# Schematic_1.net
KiCad netlist of a schematic drawn in Altium Designer
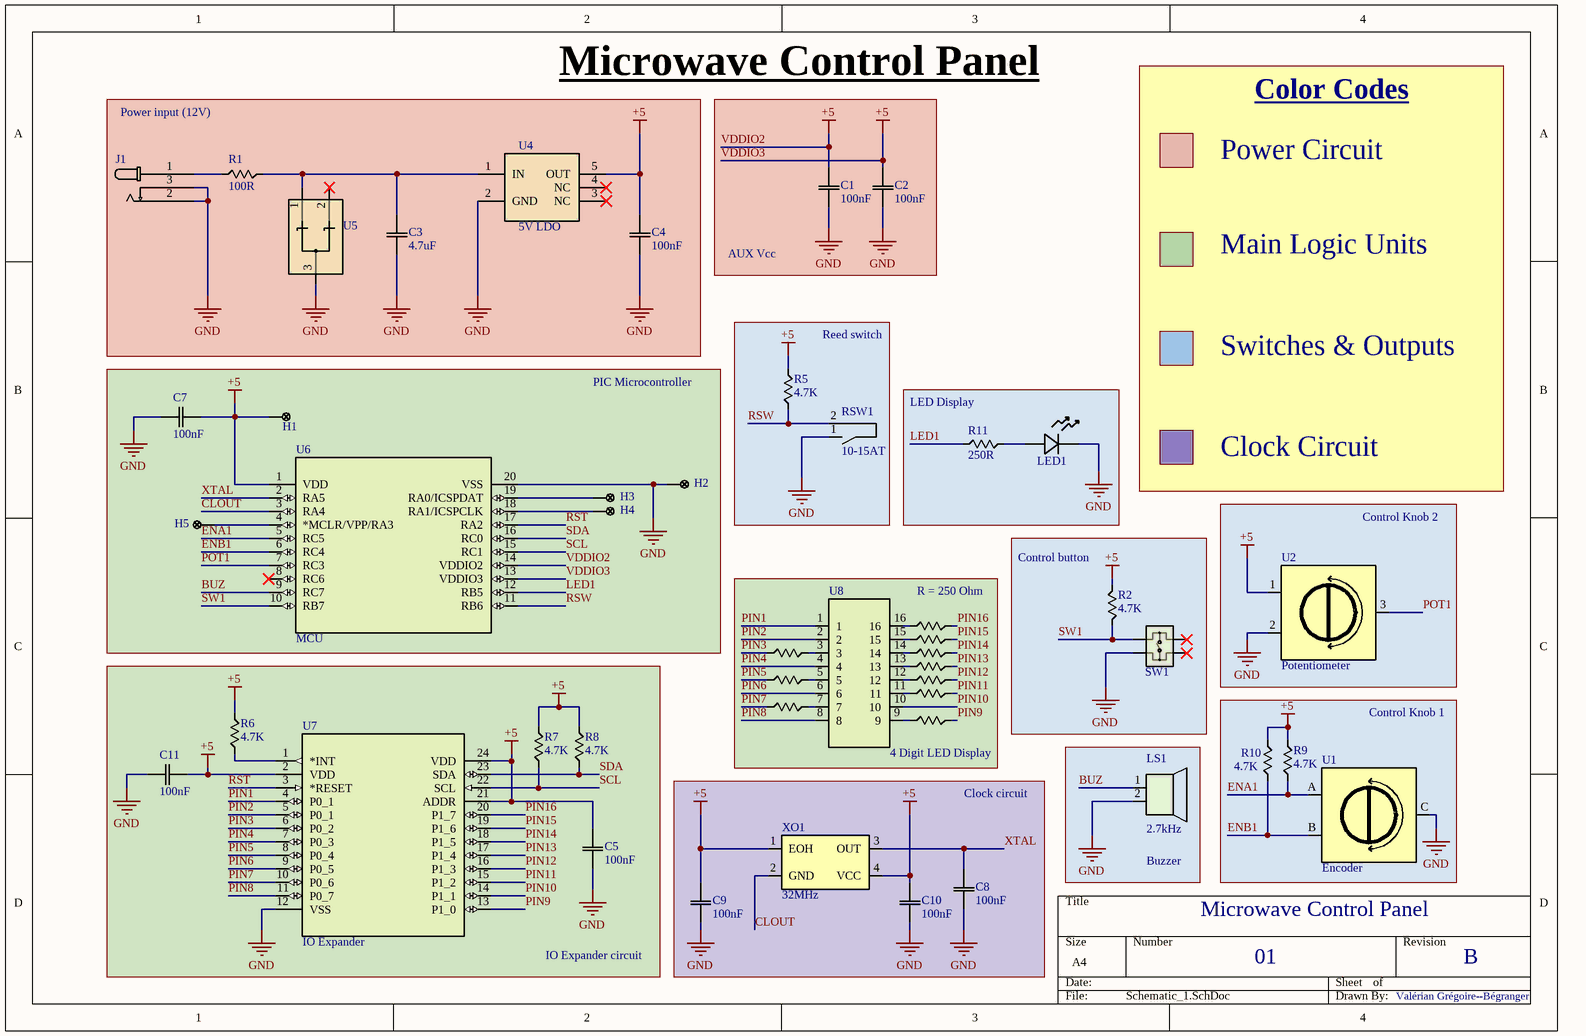
[diagram p0: Schematic_1.SchDoc]

(export (version "E")
  (design (tool "Eeschema 10.0.6"))
  (components
    (comp (ref "C1")
      (value "100nF")
      (footprint "0805_AVX")
      (libsource (lib "Schematic_Library_1") (part "08051C103JAT2A"))
    )
    (comp (ref "C2")
      (value "100nF")
      (footprint "0805_AVX")
      (libsource (lib "Schematic_Library_1") (part "08051C103JAT2A"))
    )
    (comp (ref "C3")
      (value "4.7uF")
      (footprint "CAP_08051A0R8CAT2A_AVX")
      (libsource (lib "Schematic_Library_1") (part "08053C472K4Z2A"))
    )
    (comp (ref "C4")
      (value "100nF")
      (footprint "0805_AVX")
      (libsource (lib "Schematic_Library_1") (part "08051C103JAT2A"))
    )
    (comp (ref "C5")
      (value "100nF")
      (footprint "0805_AVX")
      (libsource (lib "Schematic_Library_1") (part "08051C103JAT2A"))
    )
    (comp (ref "C7")
      (value "100nF")
      (footprint "0805_AVX")
      (libsource (lib "Schematic_Library_1") (part "08051C103JAT2A"))
    )
    (comp (ref "C8")
      (value "100nF")
      (footprint "0805_AVX")
      (libsource (lib "Schematic_Library_1") (part "08051C103JAT2A"))
    )
    (comp (ref "C9")
      (value "100nF")
      (footprint "0805_AVX")
      (libsource (lib "Schematic_Library_1") (part "08051C103JAT2A"))
    )
    (comp (ref "C10")
      (value "100nF")
      (footprint "0805_AVX")
      (libsource (lib "Schematic_Library_1") (part "08051C103JAT2A"))
    )
    (comp (ref "C11")
      (value "100nF")
      (footprint "0805_AVX")
      (libsource (lib "Schematic_Library_1") (part "08051C103JAT2A"))
    )
    (comp (ref "H1")
      (value "Output")
      (footprint "1 pin header")
      (libsource (lib "Schematic_Library_1") (part "1 pin header"))
    )
    (comp (ref "H2")
      (value "Output")
      (footprint "1 pin header")
      (libsource (lib "Schematic_Library_1") (part "1 pin header"))
    )
    (comp (ref "H3")
      (value "Output")
      (footprint "1 pin header")
      (libsource (lib "Schematic_Library_1") (part "1 pin header"))
    )
    (comp (ref "H4")
      (value "Output")
      (footprint "1 pin header")
      (libsource (lib "Schematic_Library_1") (part "1 pin header"))
    )
    (comp (ref "H5")
      (value "Output")
      (footprint "1 pin header")
      (libsource (lib "Schematic_Library_1") (part "1 pin header"))
    )
    (comp (ref "J1")
      (value "PJ-002A")
      (footprint "PJ-002A_CUD")
      (description "DC power plug")
      (libsource (lib "Schematic_Library_1") (part "PJ-002A"))
    )
    (comp (ref "LED1")
      (value "156120VS75300")
      (footprint "LED_VS75300_WRE")
      (description "LED")
      (libsource (lib "Schematic_Library_1") (part "156120VS75300"))
    )
    (comp (ref "LS1")
      (value "2.7kHz")
      (footprint "CMI-9605IC_CUD")
      (description "Buzzer")
      (libsource (lib "Schematic_Library_1") (part "CMI-9605IC-0380T"))
    )
    (comp (ref "R1")
      (value "100R")
      (footprint "0805_VIS")
      (libsource (lib "Schematic_Library_1") (part "RCG080510R0FKEA"))
    )
    (comp (ref "R2")
      (value "4.7K")
      (footprint "RES_1220_SUS")
      (libsource (lib "Schematic_Library_1") (part "RG2012P-472-B-T5"))
    )
    (comp (ref "R3")
      (value "250R")
      (footprint "0805_VIS")
      (libsource (lib "Schematic_Library_1") (part "RNCF0805TKY250R"))
    )
    (comp (ref "R4")
      (value "250R")
      (footprint "0805_VIS")
      (libsource (lib "Schematic_Library_1") (part "RNCF0805TKY250R"))
    )
    (comp (ref "R5")
      (value "4.7K")
      (footprint "RES_1220_SUS")
      (libsource (lib "Schematic_Library_1") (part "RG2012P-472-B-T5"))
    )
    (comp (ref "R6")
      (value "4.7K")
      (footprint "RES_1220_SUS")
      (libsource (lib "Schematic_Library_1") (part "RG2012P-472-B-T5"))
    )
    (comp (ref "R7")
      (value "4.7K")
      (footprint "RES_1220_SUS")
      (libsource (lib "Schematic_Library_1") (part "RG2012P-472-B-T5"))
    )
    (comp (ref "R8")
      (value "4.7K")
      (footprint "RES_1220_SUS")
      (libsource (lib "Schematic_Library_1") (part "RG2012P-472-B-T5"))
    )
    (comp (ref "R9")
      (value "4.7K")
      (footprint "RES_1220_SUS")
      (libsource (lib "Schematic_Library_1") (part "RG2012P-472-B-T5"))
    )
    (comp (ref "R10")
      (value "4.7K")
      (footprint "RES_1220_SUS")
      (libsource (lib "Schematic_Library_1") (part "RG2012P-472-B-T5"))
    )
    (comp (ref "R11")
      (value "250R")
      (footprint "0805_VIS")
      (libsource (lib "Schematic_Library_1") (part "RNCF0805TKY250R"))
    )
    (comp (ref "R12")
      (value "250R")
      (footprint "0805_VIS")
      (libsource (lib "Schematic_Library_1") (part "RNCF0805TKY250R"))
    )
    (comp (ref "R13")
      (value "250R")
      (footprint "0805_VIS")
      (libsource (lib "Schematic_Library_1") (part "RNCF0805TKY250R"))
    )
    (comp (ref "R14")
      (value "250R")
      (footprint "0805_VIS")
      (libsource (lib "Schematic_Library_1") (part "RNCF0805TKY250R"))
    )
    (comp (ref "R15")
      (value "250R")
      (footprint "0805_VIS")
      (libsource (lib "Schematic_Library_1") (part "RNCF0805TKY250R"))
    )
    (comp (ref "R16")
      (value "250R")
      (footprint "0805_VIS")
      (libsource (lib "Schematic_Library_1") (part "RNCF0805TKY250R"))
    )
    (comp (ref "R17")
      (value "250R")
      (footprint "0805_VIS")
      (libsource (lib "Schematic_Library_1") (part "RNCF0805TKY250R"))
    )
    (comp (ref "R18")
      (value "250R")
      (footprint "0805_VIS")
      (libsource (lib "Schematic_Library_1") (part "RNCF0805TKY250R"))
    )
    (comp (ref "R19")
      (value "250R")
      (footprint "0805_VIS")
      (libsource (lib "Schematic_Library_1") (part "RNCF0805TKY250R"))
    )
    (comp (ref "RSW1")
      (value "10-15AT")
      (footprint "GP56010-15")
      (description "Reed switch")
      (libsource (lib "Schematic_Library_1") (part "GP56010-15"))
    )
    (comp (ref "SW1")
      (value "TS02-66-160-BK-100-LCR-D")
      (footprint "TS02-66-160-BK-100-LCR-D")
      (description "Push button")
      (libsource (lib "Schematic_Library_1") (part "TS02-66-160-BK-100-LCR-D"))
    )
    (comp (ref "U1")
      (value "Encoder")
      (footprint "288T232R161A1")
      (description "2b Encoder")
      (libsource (lib "Schematic_Library_1") (part "288T232R161A1"))
    )
    (comp (ref "U2")
      (value "Potentiometer")
      (footprint "2002111655")
      (libsource (lib "Schematic_Library_1") (part "2002111655"))
    )
    (comp (ref "U4")
      (value "5V LDO")
      (footprint "SOT-23-5-DBV_TEX")
      (libsource (lib "Schematic_Library_1") (part "TPS7B92050DBVR"))
    )
    (comp (ref "U5")
      (value "MMBZ16VAT-QR")
      (footprint "SOT_SM712")
      (description "13V TVS")
      (libsource (lib "Schematic_Library_1") (part "MMBZ16VAT-QR"))
    )
    (comp (ref "U6")
      (value "MCU")
      (footprint "SOIC20_SO_MCH")
      (description "PIC MCU")
      (libsource (lib "Schematic_Library_1") (part "PIC18F15Q20T-ISO"))
    )
    (comp (ref "U7")
      (value "IO Expander")
      (footprint "TSSOP24_4P5X7P9_NXP")
      (description "16 I/O expander")
      (libsource (lib "Schematic_Library_1") (part "PCAL6416APW"))
    )
    (comp (ref "U8")
      (value "LED Display")
      (footprint "TDCG1060M_VIS")
      (description "4 digit LED display")
      (libsource (lib "Schematic_Library_1") (part "TDCR1060M"))
    )
    (comp (ref "XO1")
      (value "32MHz")
      (footprint "CB3-3C-64M0000")
      (description "32MHz Clock")
      (libsource (lib "Schematic_Library_1") (part "FO7HHADM320-T1"))
    )
  )
  (nets
    (net (code "1") (name "+5") (class "Default")
      (node (ref "C1") (pin "2") (pinfunction "2_2") (pintype "passive"))
      (node (ref "C10") (pin "2") (pinfunction "2_2") (pintype "passive"))
      (node (ref "C11") (pin "2") (pinfunction "2_2") (pintype "passive"))
      (node (ref "C2") (pin "2") (pinfunction "2_2") (pintype "passive"))
      (node (ref "C4") (pin "2") (pinfunction "2_2") (pintype "passive"))
      (node (ref "C5") (pin "2") (pinfunction "2_2") (pintype "passive"))
      (node (ref "C7") (pin "2") (pinfunction "2_2") (pintype "passive"))
      (node (ref "C9") (pin "2") (pinfunction "2_2") (pintype "passive"))
      (node (ref "H1") (pin "1") (pinfunction "1_1") (pintype "passive"))
      (node (ref "R10") (pin "2") (pinfunction "2_2") (pintype "passive"))
      (node (ref "R2") (pin "2") (pinfunction "2_2") (pintype "passive"))
      (node (ref "R5") (pin "2") (pinfunction "2_2") (pintype "passive"))
      (node (ref "R6") (pin "2") (pinfunction "2_2") (pintype "passive"))
      (node (ref "R7") (pin "2") (pinfunction "2_2") (pintype "passive"))
      (node (ref "R8") (pin "2") (pinfunction "2_2") (pintype "passive"))
      (node (ref "R9") (pin "2") (pinfunction "2_2") (pintype "passive"))
      (node (ref "U2") (pin "1") (pinfunction "1_1") (pintype "passive"))
      (node (ref "U4") (pin "5") (pinfunction "OUT_5") (pintype "passive"))
      (node (ref "U6") (pin "1") (pinfunction "VDD_1") (pintype "passive"))
      (node (ref "U6") (pin "13") (pinfunction "VDDIO3_13") (pintype "bidirectional"))
      (node (ref "U6") (pin "14") (pinfunction "VDDIO2_14") (pintype "bidirectional"))
      (node (ref "U7") (pin "2") (pinfunction "VDD_2") (pintype "passive"))
      (node (ref "U7") (pin "21") (pinfunction "ADDR_21") (pintype "passive"))
      (node (ref "U7") (pin "24") (pinfunction "VDD_24") (pintype "passive"))
      (node (ref "XO1") (pin "1") (pinfunction "EOH_1") (pintype "passive"))
      (node (ref "XO1") (pin "4") (pinfunction "VCC_4") (pintype "passive"))
    )
    (net (code "2") (name "/BUZ") (class "Default")
      (node (ref "LS1") (pin "1") (pinfunction "1_1") (pintype "passive"))
      (node (ref "U6") (pin "9") (pinfunction "RC7_9") (pintype "bidirectional"))
    )
    (net (code "3") (name "/CLOUT") (class "Default")
      (node (ref "U6") (pin "3") (pinfunction "RA4_3") (pintype "bidirectional"))
      (node (ref "XO1") (pin "2") (pinfunction "GND_2") (pintype "passive"))
    )
    (net (code "4") (name "/ENA1") (class "Default")
      (node (ref "R9") (pin "1") (pinfunction "1_1") (pintype "passive"))
      (node (ref "U1") (pin "A") (pinfunction "A_A") (pintype "passive"))
      (node (ref "U6") (pin "5") (pinfunction "RC5_5") (pintype "bidirectional"))
    )
    (net (code "5") (name "/ENB1") (class "Default")
      (node (ref "R10") (pin "1") (pinfunction "1_1") (pintype "passive"))
      (node (ref "U1") (pin "B") (pinfunction "B_B") (pintype "passive"))
      (node (ref "U6") (pin "6") (pinfunction "RC4_6") (pintype "bidirectional"))
    )
    (net (code "6") (name "/LED1") (class "Default")
      (node (ref "R11") (pin "1") (pinfunction "1_1") (pintype "passive"))
      (node (ref "U6") (pin "12") (pinfunction "RB5_12") (pintype "bidirectional"))
    )
    (net (code "7") (name "/PIN1") (class "Default")
      (node (ref "U7") (pin "4") (pinfunction "P0_1_4") (pintype "bidirectional"))
      (node (ref "U8") (pin "1") (pinfunction "1_1") (pintype "passive"))
    )
    (net (code "8") (name "/PIN2") (class "Default")
      (node (ref "U7") (pin "5") (pinfunction "P0_1_5") (pintype "bidirectional"))
      (node (ref "U8") (pin "2") (pinfunction "2_2") (pintype "passive"))
    )
    (net (code "9") (name "/PIN3") (class "Default")
      (node (ref "R12") (pin "1") (pinfunction "1_1") (pintype "passive"))
      (node (ref "U7") (pin "6") (pinfunction "P0_2_6") (pintype "bidirectional"))
    )
    (net (code "10") (name "/PIN4") (class "Default")
      (node (ref "U7") (pin "7") (pinfunction "P0_3_7") (pintype "bidirectional"))
      (node (ref "U8") (pin "4") (pinfunction "4_4") (pintype "passive"))
    )
    (net (code "11") (name "/PIN5") (class "Default")
      (node (ref "R15") (pin "1") (pinfunction "1_1") (pintype "passive"))
      (node (ref "U7") (pin "8") (pinfunction "P0_4_8") (pintype "bidirectional"))
    )
    (net (code "12") (name "/PIN6") (class "Default")
      (node (ref "U7") (pin "9") (pinfunction "P0_5_9") (pintype "bidirectional"))
      (node (ref "U8") (pin "6") (pinfunction "6_6") (pintype "passive"))
    )
    (net (code "13") (name "/PIN7") (class "Default")
      (node (ref "R18") (pin "1") (pinfunction "1_1") (pintype "passive"))
      (node (ref "U7") (pin "10") (pinfunction "P0_6_10") (pintype "bidirectional"))
    )
    (net (code "14") (name "/PIN8") (class "Default")
      (node (ref "U7") (pin "11") (pinfunction "P0_7_11") (pintype "bidirectional"))
      (node (ref "U8") (pin "8") (pinfunction "8_8") (pintype "passive"))
    )
    (net (code "15") (name "/PIN9") (class "Default")
      (node (ref "R19") (pin "2") (pinfunction "2_2") (pintype "passive"))
      (node (ref "U7") (pin "13") (pinfunction "P1_0_13") (pintype "bidirectional"))
    )
    (net (code "16") (name "/PIN10") (class "Default")
      (node (ref "U7") (pin "14") (pinfunction "P1_1_14") (pintype "bidirectional"))
      (node (ref "U8") (pin "10") (pinfunction "10_10") (pintype "passive"))
    )
    (net (code "17") (name "/PIN11") (class "Default")
      (node (ref "R17") (pin "2") (pinfunction "2_2") (pintype "passive"))
      (node (ref "U7") (pin "15") (pinfunction "P1_2_15") (pintype "bidirectional"))
    )
    (net (code "18") (name "/PIN12") (class "Default")
      (node (ref "R16") (pin "2") (pinfunction "2_2") (pintype "passive"))
      (node (ref "U7") (pin "16") (pinfunction "P1_3_16") (pintype "bidirectional"))
    )
    (net (code "19") (name "/PIN13") (class "Default")
      (node (ref "R14") (pin "2") (pinfunction "2_2") (pintype "passive"))
      (node (ref "U7") (pin "17") (pinfunction "P1_4_17") (pintype "bidirectional"))
    )
    (net (code "20") (name "/PIN14") (class "Default")
      (node (ref "R13") (pin "2") (pinfunction "2_2") (pintype "passive"))
      (node (ref "U7") (pin "18") (pinfunction "P1_5_18") (pintype "bidirectional"))
    )
    (net (code "21") (name "/PIN15") (class "Default")
      (node (ref "R4") (pin "2") (pinfunction "2_2") (pintype "passive"))
      (node (ref "U7") (pin "19") (pinfunction "P1_6_19") (pintype "bidirectional"))
    )
    (net (code "22") (name "/PIN16") (class "Default")
      (node (ref "R3") (pin "2") (pinfunction "2_2") (pintype "passive"))
      (node (ref "U7") (pin "20") (pinfunction "P1_7_20") (pintype "bidirectional"))
    )
    (net (code "23") (name "/POT1") (class "Default")
      (node (ref "U2") (pin "3") (pinfunction "3_3") (pintype "passive"))
      (node (ref "U6") (pin "7") (pinfunction "RC3_7") (pintype "bidirectional"))
    )
    (net (code "24") (name "/RST") (class "Default")
      (node (ref "U6") (pin "17") (pinfunction "RA2_17") (pintype "bidirectional"))
      (node (ref "U7") (pin "3") (pinfunction "*RESET_3") (pintype "input"))
    )
    (net (code "25") (name "/RSW") (class "Default")
      (node (ref "R5") (pin "1") (pinfunction "1_1") (pintype "passive"))
      (node (ref "RSW1") (pin "2") (pinfunction "2_2") (pintype "passive"))
      (node (ref "U6") (pin "11") (pinfunction "RB6_11") (pintype "bidirectional"))
    )
    (net (code "26") (name "/SCL") (class "Default")
      (node (ref "R7") (pin "1") (pinfunction "1_1") (pintype "passive"))
      (node (ref "U6") (pin "15") (pinfunction "RC1_15") (pintype "bidirectional"))
      (node (ref "U7") (pin "22") (pinfunction "SCL_22") (pintype "input"))
    )
    (net (code "27") (name "/SDA") (class "Default")
      (node (ref "R8") (pin "1") (pinfunction "1_1") (pintype "passive"))
      (node (ref "U6") (pin "16") (pinfunction "RC0_16") (pintype "bidirectional"))
      (node (ref "U7") (pin "23") (pinfunction "SDA_23") (pintype "bidirectional"))
    )
    (net (code "28") (name "/SW1") (class "Default")
      (node (ref "R2") (pin "1") (pinfunction "1_1") (pintype "passive"))
      (node (ref "SW1") (pin "1") (pinfunction "2_1") (pintype "passive"))
      (node (ref "U6") (pin "10") (pinfunction "RB7_10") (pintype "bidirectional"))
    )
    (net (code "29") (name "/XTAL") (class "Default")
      (node (ref "C8") (pin "2") (pinfunction "2_2") (pintype "passive"))
      (node (ref "U6") (pin "2") (pinfunction "RA5_2") (pintype "bidirectional"))
      (node (ref "XO1") (pin "3") (pinfunction "OUT_3") (pintype "passive"))
    )
    (net (code "30") (name "GND") (class "Default")
      (node (ref "C1") (pin "1") (pinfunction "1_1") (pintype "passive"))
      (node (ref "C10") (pin "1") (pinfunction "1_1") (pintype "passive"))
      (node (ref "C11") (pin "1") (pinfunction "1_1") (pintype "passive"))
      (node (ref "C2") (pin "1") (pinfunction "1_1") (pintype "passive"))
      (node (ref "C3") (pin "1") (pinfunction "1_1") (pintype "passive"))
      (node (ref "C4") (pin "1") (pinfunction "1_1") (pintype "passive"))
      (node (ref "C5") (pin "1") (pinfunction "1_1") (pintype "passive"))
      (node (ref "C7") (pin "1") (pinfunction "1_1") (pintype "passive"))
      (node (ref "C8") (pin "1") (pinfunction "1_1") (pintype "passive"))
      (node (ref "C9") (pin "1") (pinfunction "1_1") (pintype "passive"))
      (node (ref "H2") (pin "1") (pinfunction "1_1") (pintype "passive"))
      (node (ref "J1") (pin "2") (pinfunction "2_2") (pintype "passive"))
      (node (ref "J1") (pin "3") (pinfunction "3_3") (pintype "passive"))
      (node (ref "LED1") (pin "1") (pinfunction "1_1") (pintype "passive"))
      (node (ref "LS1") (pin "2") (pinfunction "2_2") (pintype "passive"))
      (node (ref "RSW1") (pin "1") (pinfunction "1_1") (pintype "passive"))
      (node (ref "SW1") (pin "2") (pinfunction "4_2") (pintype "passive"))
      (node (ref "U1") (pin "C") (pinfunction "C_C") (pintype "passive"))
      (node (ref "U2") (pin "2") (pinfunction "2_2") (pintype "passive"))
      (node (ref "U4") (pin "2") (pinfunction "GND_2") (pintype "power_in"))
      (node (ref "U5") (pin "3") (pinfunction "3_3") (pintype "passive"))
      (node (ref "U6") (pin "20") (pinfunction "VSS_20") (pintype "passive"))
      (node (ref "U7") (pin "12") (pinfunction "VSS_12") (pintype "power_in"))
    )
    (net (code "31") (name "Net-(J1-Pad1)") (class "Default")
      (node (ref "J1") (pin "1") (pinfunction "1_1") (pintype "passive"))
      (node (ref "R1") (pin "1") (pinfunction "1_1") (pintype "passive"))
    )
    (net (code "32") (name "Net-(LED1-Pad2)") (class "Default")
      (node (ref "LED1") (pin "2") (pinfunction "2_2") (pintype "passive"))
      (node (ref "R11") (pin "2") (pinfunction "2_2") (pintype "passive"))
    )
    (net (code "33") (name "Net-(R3-Pad1)") (class "Default")
      (node (ref "R3") (pin "1") (pinfunction "1_1") (pintype "passive"))
      (node (ref "U8") (pin "16") (pinfunction "16_16") (pintype "passive"))
    )
    (net (code "34") (name "Net-(R4-Pad1)") (class "Default")
      (node (ref "R4") (pin "1") (pinfunction "1_1") (pintype "passive"))
      (node (ref "U8") (pin "15") (pinfunction "15_15") (pintype "passive"))
    )
    (net (code "35") (name "Net-(R12-Pad2)") (class "Default")
      (node (ref "R12") (pin "2") (pinfunction "2_2") (pintype "passive"))
      (node (ref "U8") (pin "3") (pinfunction "3_3") (pintype "passive"))
    )
    (net (code "36") (name "Net-(R13-Pad1)") (class "Default")
      (node (ref "R13") (pin "1") (pinfunction "1_1") (pintype "passive"))
      (node (ref "U8") (pin "14") (pinfunction "14_14") (pintype "passive"))
    )
    (net (code "37") (name "Net-(R14-Pad1)") (class "Default")
      (node (ref "R14") (pin "1") (pinfunction "1_1") (pintype "passive"))
      (node (ref "U8") (pin "13") (pinfunction "13_13") (pintype "passive"))
    )
    (net (code "38") (name "Net-(R15-Pad2)") (class "Default")
      (node (ref "R15") (pin "2") (pinfunction "2_2") (pintype "passive"))
      (node (ref "U8") (pin "5") (pinfunction "5_5") (pintype "passive"))
    )
    (net (code "39") (name "Net-(R16-Pad1)") (class "Default")
      (node (ref "R16") (pin "1") (pinfunction "1_1") (pintype "passive"))
      (node (ref "U8") (pin "12") (pinfunction "12_12") (pintype "passive"))
    )
    (net (code "40") (name "Net-(R17-Pad1)") (class "Default")
      (node (ref "R17") (pin "1") (pinfunction "1_1") (pintype "passive"))
      (node (ref "U8") (pin "11") (pinfunction "11_11") (pintype "passive"))
    )
    (net (code "41") (name "Net-(R18-Pad2)") (class "Default")
      (node (ref "R18") (pin "2") (pinfunction "2_2") (pintype "passive"))
      (node (ref "U8") (pin "7") (pinfunction "7_7") (pintype "passive"))
    )
    (net (code "42") (name "Net-(R19-Pad1)") (class "Default")
      (node (ref "R19") (pin "1") (pinfunction "1_1") (pintype "passive"))
      (node (ref "U8") (pin "9") (pinfunction "9_9") (pintype "passive"))
    )
    (net (code "43") (name "Net-(U4-IN)") (class "Default")
      (node (ref "C3") (pin "2") (pinfunction "2_2") (pintype "passive"))
      (node (ref "R1") (pin "2") (pinfunction "2_2") (pintype "passive"))
      (node (ref "U4") (pin "1") (pinfunction "IN_1") (pintype "passive"))
      (node (ref "U5") (pin "1") (pinfunction "1_1") (pintype "passive"))
    )
    (net (code "44") (name "Net-(U6-*MCLR{slash}VPP{slash}RA3)") (class "Default")
      (node (ref "H5") (pin "1") (pinfunction "1_1") (pintype "passive"))
      (node (ref "U6") (pin "4") (pinfunction "*MCLR/VPP/RA3_4") (pintype "bidirectional"))
    )
    (net (code "45") (name "Net-(U6-RA0{slash}ICSPDAT)") (class "Default")
      (node (ref "H3") (pin "1") (pinfunction "1_1") (pintype "passive"))
      (node (ref "U6") (pin "19") (pinfunction "RA0/ICSPDAT_19") (pintype "bidirectional"))
    )
    (net (code "46") (name "Net-(U6-RA1{slash}ICSPCLK)") (class "Default")
      (node (ref "H4") (pin "1") (pinfunction "1_1") (pintype "passive"))
      (node (ref "U6") (pin "18") (pinfunction "RA1/ICSPCLK_18") (pintype "bidirectional"))
    )
    (net (code "47") (name "Net-(U7-*INT)") (class "Default")
      (node (ref "R6") (pin "1") (pinfunction "1_1") (pintype "passive"))
      (node (ref "U7") (pin "1") (pinfunction "*INT_1") (pintype "output"))
    )
    (net (code "48") (name "unconnected-(SW1-3-Pad2)") (class "Default")
      (node (ref "SW1") (pin "2") (pinfunction "3_2") (pintype "passive+no_connect"))
    )
    (net (code "49") (name "unconnected-(SW1-Pad1)") (class "Default")
      (node (ref "SW1") (pin "1") (pinfunction "1_1") (pintype "passive+no_connect"))
    )
    (net (code "50") (name "unconnected-(U4-NC-Pad3)") (class "Default")
      (node (ref "U4") (pin "3") (pinfunction "NC_3") (pintype "passive+no_connect"))
    )
    (net (code "51") (name "unconnected-(U4-NC-Pad4)") (class "Default")
      (node (ref "U4") (pin "4") (pinfunction "NC_4") (pintype "passive+no_connect"))
    )
    (net (code "52") (name "unconnected-(U5-Pad2)") (class "Default")
      (node (ref "U5") (pin "2") (pinfunction "2_2") (pintype "passive+no_connect"))
    )
    (net (code "53") (name "unconnected-(U6-RC6-Pad8)") (class "Default")
      (node (ref "U6") (pin "8") (pinfunction "RC6_8") (pintype "bidirectional+no_connect"))
    )
  )
)
